# SENSOR_BOARDS.net
KiCad netlist of a schematic drawn in Altium Designer
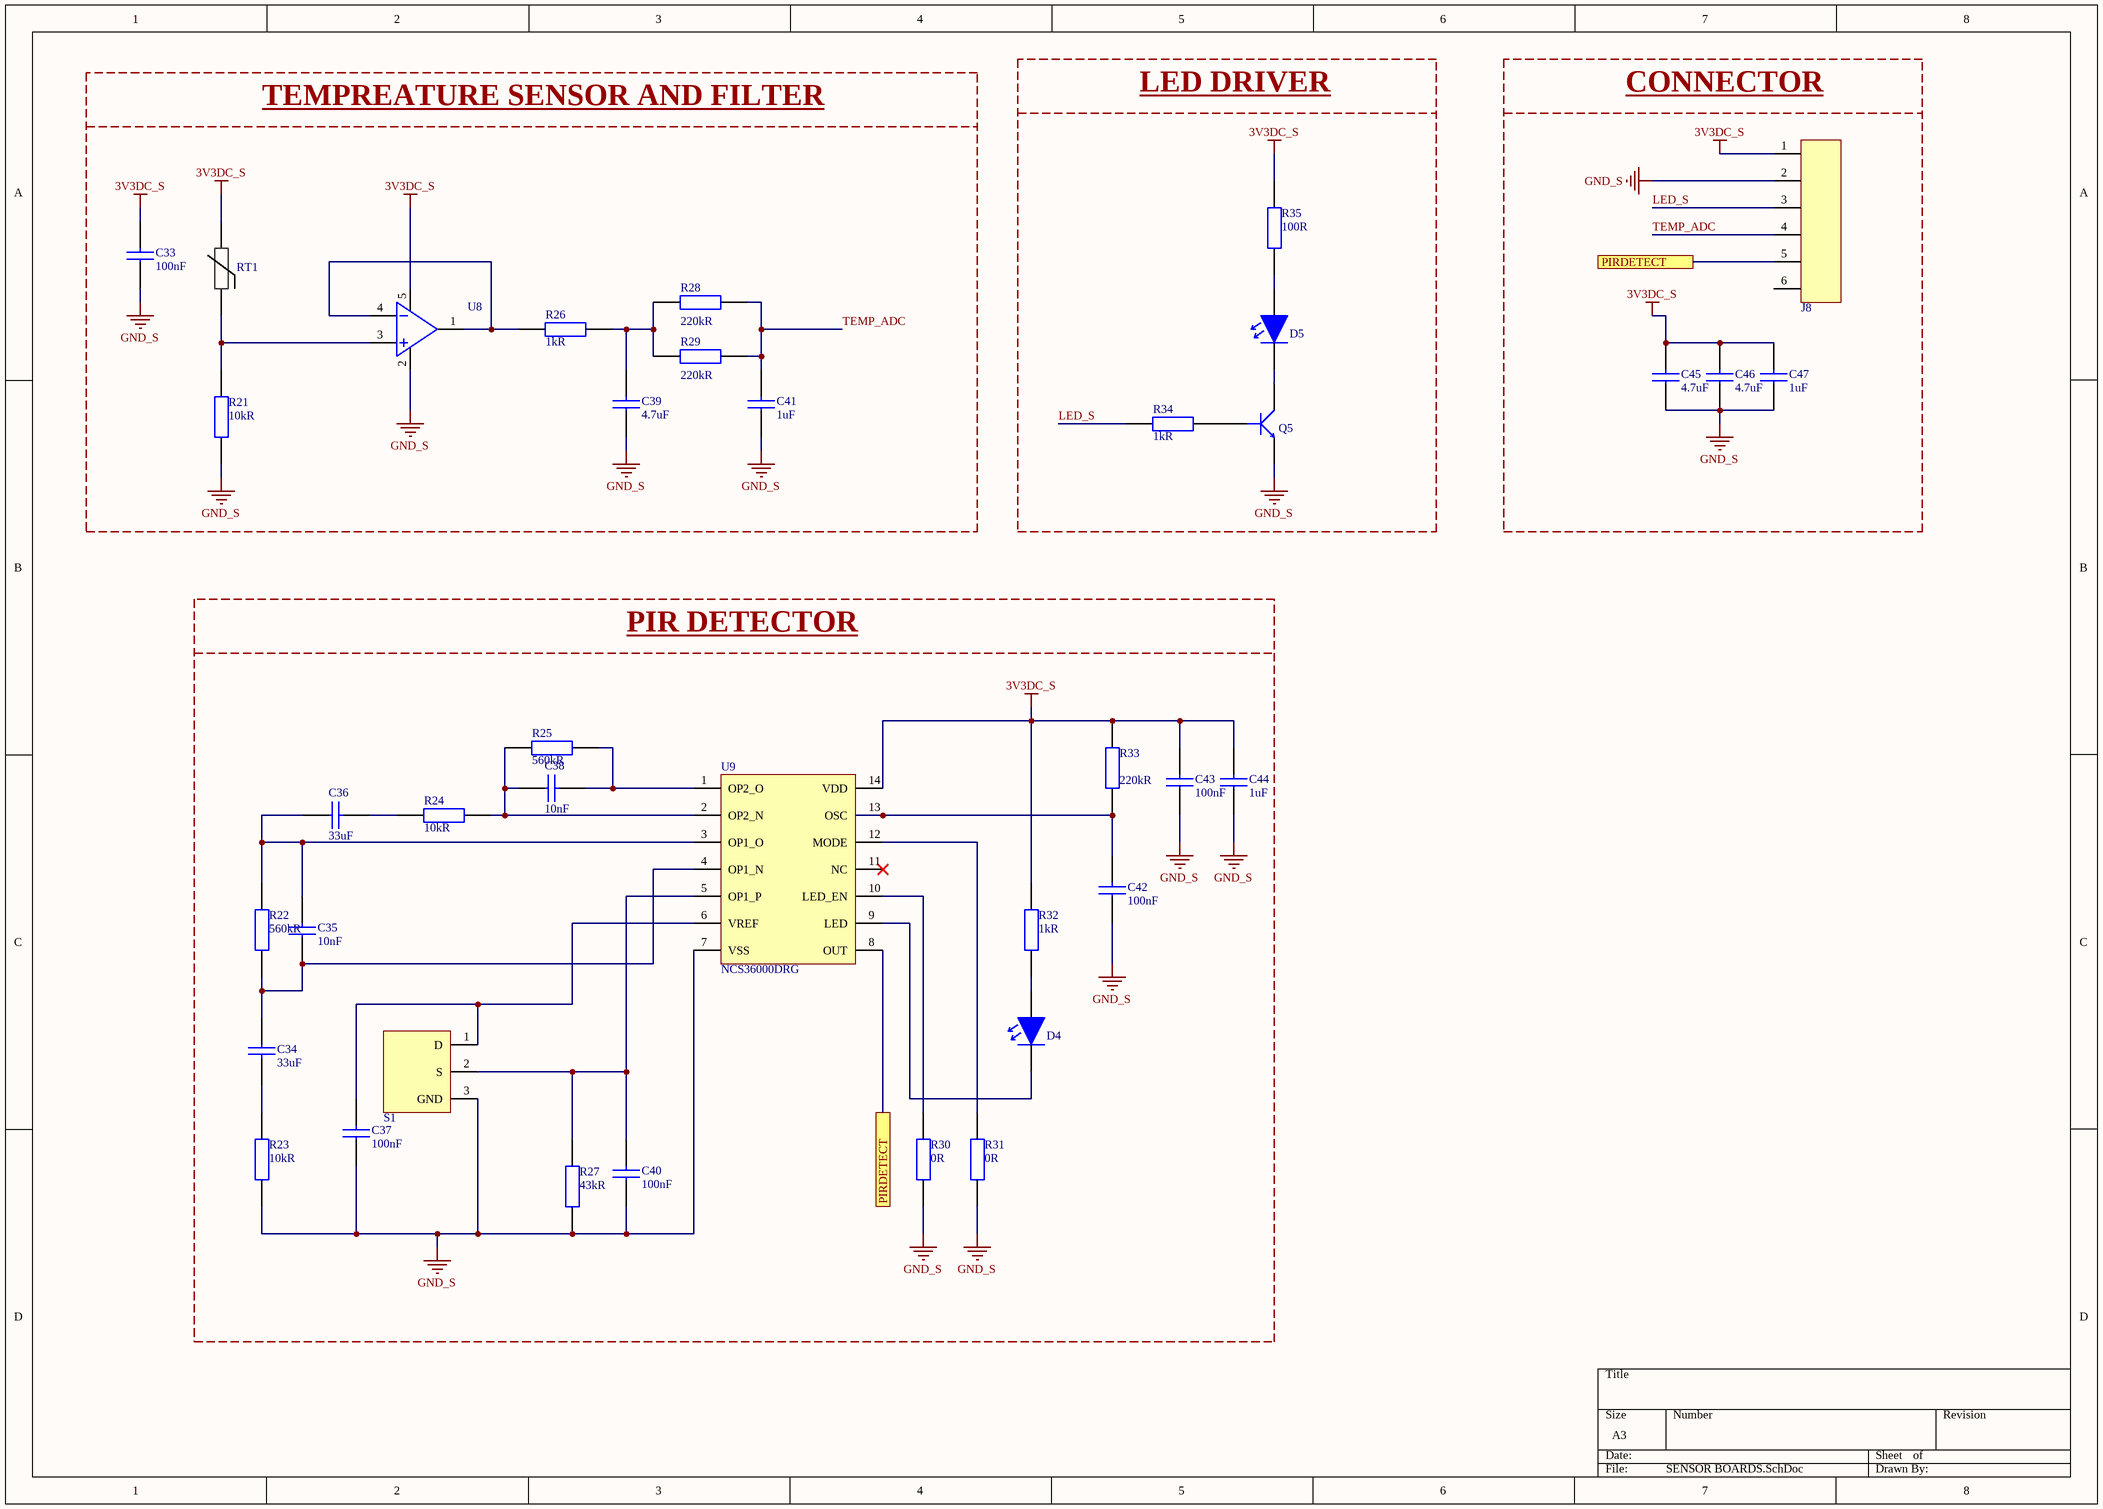
[diagram p0: SENSOR BOARDS.SchDoc]

(export (version "E")
  (design (tool "Eeschema 10.0.6"))
  (components
    (comp (ref "C33")
      (value "C0603C104K5RACTU")
      (footprint "CAP_0603")
      (description "CAP CER 100nF %10 0603 SMD")
      (fields
        (field (name "MANUFACTURER") "KEMET")
        (field (name "TOLERANCE") "10%")
        (field (name "CAPACITANCE") "100nF")
        (field (name "DESIGNED BY") "BERK")
      )
      (libsource (lib "UDEMY_Library") (part "CAP CER 100nF 0603"))
    )
    (comp (ref "C34")
      (value "C3216X5R1E336M160AC")
      (footprint "CAP_1206")
      (description "CAP CER 33uF %20 1206 SMD")
      (fields
        (field (name "MANUFACTURER") "TDK")
        (field (name "TOLERANCE") "20%")
        (field (name "CAPACITANCE") "33uF")
        (field (name "DESIGNED BY") "BERK")
      )
      (libsource (lib "UDEMY_Library") (part "CAP CER 33uF 1206"))
    )
    (comp (ref "C35")
      (value "0603B103K160CT")
      (footprint "CAP_0603")
      (description "CAP CER 10nF %10 0603")
      (fields
        (field (name "MANUFACTURER") "Walsin Technologies")
        (field (name "TOLERANCE") "10%")
        (field (name "CAPACITANCE") "10nF")
        (field (name "DESIGNED BY") "BERK")
      )
      (libsource (lib "UDEMY_Library") (part "CAP CER 10nF 0603"))
    )
    (comp (ref "C36")
      (value "C3216X5R1E336M160AC")
      (footprint "CAP_1206")
      (description "CAP CER 33uF %20 1206 SMD")
      (fields
        (field (name "MANUFACTURER") "TDK")
        (field (name "TOLERANCE") "20%")
        (field (name "CAPACITANCE") "33uF")
        (field (name "DESIGNED BY") "BERK")
      )
      (libsource (lib "UDEMY_Library") (part "CAP CER 33uF 1206"))
    )
    (comp (ref "C37")
      (value "C0603C104K5RACTU")
      (footprint "CAP_0603")
      (description "CAP CER 100nF %10 0603 SMD")
      (fields
        (field (name "MANUFACTURER") "KEMET")
        (field (name "TOLERANCE") "10%")
        (field (name "CAPACITANCE") "100nF")
        (field (name "DESIGNED BY") "BERK")
      )
      (libsource (lib "UDEMY_Library") (part "CAP CER 100nF 0603"))
    )
    (comp (ref "C38")
      (value "0603B103K160CT")
      (footprint "CAP_0603")
      (description "CAP CER 10nF %10 0603")
      (fields
        (field (name "MANUFACTURER") "Walsin Technologies")
        (field (name "TOLERANCE") "10%")
        (field (name "CAPACITANCE") "10nF")
        (field (name "DESIGNED BY") "BERK")
      )
      (libsource (lib "UDEMY_Library") (part "CAP CER 10nF 0603"))
    )
    (comp (ref "C39")
      (value "CL21A475KAQNNNE")
      (footprint "CAP_0805")
      (description "CAP CER 4.7uF %10 0805")
      (fields
        (field (name "MANUFACTURER") "Samsung")
        (field (name "TOLERANCE") "10%")
        (field (name "CAPACITANCE") "4.7uF")
        (field (name "DESIGNED BY") "BERK")
      )
      (libsource (lib "UDEMY_Library") (part "CAP CER 4.7uF 0805"))
    )
    (comp (ref "C40")
      (value "C0603C104K5RACTU")
      (footprint "CAP_0603")
      (description "CAP CER 100nF %10 0603 SMD")
      (fields
        (field (name "MANUFACTURER") "KEMET")
        (field (name "TOLERANCE") "10%")
        (field (name "CAPACITANCE") "100nF")
        (field (name "DESIGNED BY") "BERK")
      )
      (libsource (lib "UDEMY_Library") (part "CAP CER 100nF 0603"))
    )
    (comp (ref "C41")
      (value "CL21B105KBFNNNE")
      (footprint "CAP_0805")
      (description "CAP CER 1uF %10 0805")
      (fields
        (field (name "MANUFACTURER") "Samsung")
        (field (name "TOLERANCE") "10%")
        (field (name "CAPACITANCE") "1uF")
        (field (name "DESIGNED BY") "BERK")
      )
      (libsource (lib "UDEMY_Library") (part "CAP CER 1uF 0805"))
    )
    (comp (ref "C42")
      (value "C0603C104K5RACTU")
      (footprint "CAP_0603")
      (description "CAP CER 100nF %10 0603 SMD")
      (fields
        (field (name "MANUFACTURER") "KEMET")
        (field (name "TOLERANCE") "10%")
        (field (name "CAPACITANCE") "100nF")
        (field (name "DESIGNED BY") "BERK")
      )
      (libsource (lib "UDEMY_Library") (part "CAP CER 100nF 0603"))
    )
    (comp (ref "C43")
      (value "C0603C104K5RACTU")
      (footprint "CAP_0603")
      (description "CAP CER 100nF %10 0603 SMD")
      (fields
        (field (name "MANUFACTURER") "KEMET")
        (field (name "TOLERANCE") "10%")
        (field (name "CAPACITANCE") "100nF")
        (field (name "DESIGNED BY") "BERK")
      )
      (libsource (lib "UDEMY_Library") (part "CAP CER 100nF 0603"))
    )
    (comp (ref "C44")
      (value "CL21B105KBFNNNE")
      (footprint "CAP_0805")
      (description "CAP CER 1uF %10 0805")
      (fields
        (field (name "MANUFACTURER") "Samsung")
        (field (name "TOLERANCE") "10%")
        (field (name "CAPACITANCE") "1uF")
        (field (name "DESIGNED BY") "BERK")
      )
      (libsource (lib "UDEMY_Library") (part "CAP CER 1uF 0805"))
    )
    (comp (ref "C45")
      (value "CL21A475KAQNNNE")
      (footprint "CAP_0805")
      (description "CAP CER 4.7uF %10 0805")
      (fields
        (field (name "MANUFACTURER") "Samsung")
        (field (name "TOLERANCE") "10%")
        (field (name "CAPACITANCE") "4.7uF")
        (field (name "DESIGNED BY") "BERK")
      )
      (libsource (lib "UDEMY_Library") (part "CAP CER 4.7uF 0805"))
    )
    (comp (ref "C46")
      (value "CL21A475KAQNNNE")
      (footprint "CAP_0805")
      (description "CAP CER 4.7uF %10 0805")
      (fields
        (field (name "MANUFACTURER") "Samsung")
        (field (name "TOLERANCE") "10%")
        (field (name "CAPACITANCE") "4.7uF")
        (field (name "DESIGNED BY") "BERK")
      )
      (libsource (lib "UDEMY_Library") (part "CAP CER 4.7uF 0805"))
    )
    (comp (ref "C47")
      (value "CL21B105KBFNNNE")
      (footprint "CAP_0805")
      (description "CAP CER 1uF %10 0805")
      (fields
        (field (name "MANUFACTURER") "Samsung")
        (field (name "TOLERANCE") "10%")
        (field (name "CAPACITANCE") "1uF")
        (field (name "DESIGNED BY") "BERK")
      )
      (libsource (lib "UDEMY_Library") (part "CAP CER 1uF 0805"))
    )
    (comp (ref "D4")
      (value "LTST-C171GKT")
      (footprint "LED_GREEN_0805")
      (description "Green 0805 130 º Min 5 mcd Typical 12 mcd Water Clear Lens SMT LED")
      (fields (field (name "MANUFACTURER") "Vishay Lite-On") (field (name "DESIGNED BY") "BERK"))
      (libsource (lib "UDEMY_Library") (part "LED GREEN 0805"))
    )
    (comp (ref "D5")
      (value "LH R974-LP-1")
      (footprint "LED_RED_0805")
      (description "LED Uni-Color Hyper Red 660nm 2-Pin Chip 0805(2012Metric) T/R")
      (fields (field (name "MANUFACTURER") "Osram Opto") (field (name "DESIGNED BY") "BERK"))
      (libsource (lib "UDEMY_Library") (part "LED RED 0805"))
    )
    (comp (ref "J8")
      (value "64800611622")
      (footprint "64800611622")
      (description "1.50mm 6PIN Connector")
      (fields (field (name "MANUFACTURER") "Wurth Electronics"))
      (libsource (lib "UDEMY_Library") (part "64800611622_conn_6pin"))
    )
    (comp (ref "Q5")
      (value "MMBT3904-7-F")
      (footprint "SOT-23F")
      (description "Transistor General Purpose BJT NPN 40 Volt 0.2A Automotive 3-Pin SOT-23")
      (fields (field (name "MANUFACTURER") "Diodes Zetex") (field (name "DESIGNED BY") "BERK"))
      (libsource (lib "UDEMY_Library") (part "MMBT3904-7-F"))
    )
    (comp (ref "R21")
      (value "RC0603FR-0710KL")
      (footprint "RES_0603")
      (description "RES 10K %1 OHM 0603 SMD")
      (fields
        (field (name "MANUFACTURER") "Yageo")
        (field (name "TOLERANCE") "1%")
        (field (name "RESISTANCE") "10kR")
        (field (name "DESIGNED BY") "BERK")
      )
      (libsource (lib "") (part "RES 10K OHM 0603_1"))
    )
    (comp (ref "R22")
      (value "RC0603JR-07560KL")
      (footprint "RES_0603")
      (description "RES SMD 560K OHM 5% 1/10W 0603")
      (fields
        (field (name "MANUFACTURER") "Yageo")
        (field (name "TOLERANCE") "5%")
        (field (name "RESISTANCE") "560kR")
        (field (name "DESIGNED BY") "BERK")
      )
      (libsource (lib "") (part "RES 560K OHM 0603_1"))
    )
    (comp (ref "R23")
      (value "RC0603FR-0710KL")
      (footprint "RES_0603")
      (description "RES 10K %1 OHM 0603 SMD")
      (fields
        (field (name "MANUFACTURER") "Yageo")
        (field (name "TOLERANCE") "1%")
        (field (name "RESISTANCE") "10kR")
        (field (name "DESIGNED BY") "BERK")
      )
      (libsource (lib "UDEMY_Library") (part "RES 10K OHM 0603"))
    )
    (comp (ref "R24")
      (value "RC0603FR-0710KL")
      (footprint "RES_0603")
      (description "RES 10K %1 OHM 0603 SMD")
      (fields
        (field (name "MANUFACTURER") "Yageo")
        (field (name "TOLERANCE") "1%")
        (field (name "RESISTANCE") "10kR")
        (field (name "DESIGNED BY") "BERK")
      )
      (libsource (lib "") (part "RES 10K OHM 0603_2"))
    )
    (comp (ref "R25")
      (value "RC0603JR-07560KL")
      (footprint "RES_0603")
      (description "RES SMD 560K OHM 5% 1/10W 0603")
      (fields
        (field (name "MANUFACTURER") "Yageo")
        (field (name "TOLERANCE") "5%")
        (field (name "RESISTANCE") "560kR")
        (field (name "DESIGNED BY") "BERK")
      )
      (libsource (lib "UDEMY_Library") (part "RES 560K OHM 0603"))
    )
    (comp (ref "R26")
      (value "RC0603FR-0710KL")
      (footprint "RES_0603")
      (description "RES 1K %1 OHM 0603 SMD")
      (fields
        (field (name "MANUFACTURER") "Yageo")
        (field (name "MANUFACTURER PART NUMBER") "RC0603JR-071KL")
        (field (name "RESISTANCE") "1kR")
        (field (name "DESIGNED BY") "BERK")
      )
      (libsource (lib "") (part "RES 1K OHM 0603_2"))
    )
    (comp (ref "R27")
      (value "RC0603JR-0743KL")
      (footprint "RES_0603")
      (description "RES 43K %5 OHM 0603 SMD")
      (fields
        (field (name "MANUFACTURER") "Yageo")
        (field (name "TOLERANCE") "5%")
        (field (name "RESISTANCE") "43kR")
        (field (name "DESIGNED BY") "BERK")
      )
      (libsource (lib "UDEMY_Library") (part "RES 43K OHM 0603"))
    )
    (comp (ref "R28")
      (value "RC0603JR-07220KL")
      (footprint "RES_0603")
      (description "RES 220K %5 OHM 0603 SMD")
      (fields
        (field (name "MANUFACTURER") "Yageo")
        (field (name "TOLERANCE") "5%")
        (field (name "RESISTANCE") "220kR")
      )
      (libsource (lib "UDEMY_Library") (part "RES 220K OHM 0603"))
    )
    (comp (ref "R29")
      (value "RC0603JR-07220KL")
      (footprint "RES_0603")
      (description "RES 220K %5 OHM 0603 SMD")
      (fields
        (field (name "MANUFACTURER") "Yageo")
        (field (name "TOLERANCE") "5%")
        (field (name "RESISTANCE") "220kR")
      )
      (libsource (lib "UDEMY_Library") (part "RES 220K OHM 0603"))
    )
    (comp (ref "R30")
      (value "RC0603JR-070RL")
      (footprint "RES_0603")
      (description "RES 0 %1 OHM 0603 SMD")
      (fields
        (field (name "MANUFACTURER") "Yageo")
        (field (name "TOLERANCE") "1%")
        (field (name "RESISTANCE") "0R")
        (field (name "DESIGNED BY") "BERK")
      )
      (libsource (lib "UDEMY_Library") (part "RES 0 OHM 0603"))
    )
    (comp (ref "R31")
      (value "RC0603JR-070RL")
      (footprint "RES_0603")
      (description "RES 0 %1 OHM 0603 SMD")
      (fields
        (field (name "MANUFACTURER") "Yageo")
        (field (name "TOLERANCE") "1%")
        (field (name "RESISTANCE") "0R")
        (field (name "DESIGNED BY") "BERK")
      )
      (libsource (lib "UDEMY_Library") (part "RES 0 OHM 0603"))
    )
    (comp (ref "R32")
      (value "RC0603FR-0710KL")
      (footprint "RES_0603")
      (description "RES 1K %1 OHM 0603 SMD")
      (fields
        (field (name "MANUFACTURER") "Yageo")
        (field (name "MANUFACTURER PART NUMBER") "RC0603JR-071KL")
        (field (name "RESISTANCE") "1kR")
        (field (name "DESIGNED BY") "BERK")
      )
      (libsource (lib "") (part "RES 1K OHM 0603_1"))
    )
    (comp (ref "R33")
      (value "RC0603JR-07220KL")
      (footprint "RES_0603")
      (description "RES 220K %5 OHM 0603 SMD")
      (fields
        (field (name "MANUFACTURER") "Yageo")
        (field (name "TOLERANCE") "5%")
        (field (name "RESISTANCE") "220kR")
      )
      (libsource (lib "") (part "RES 220K OHM 0603_1"))
    )
    (comp (ref "R34")
      (value "RC0603FR-0710KL")
      (footprint "RES_0603")
      (description "RES 1K %1 OHM 0603 SMD")
      (fields
        (field (name "MANUFACTURER") "Yageo")
        (field (name "MANUFACTURER PART NUMBER") "RC0603JR-071KL")
        (field (name "RESISTANCE") "1kR")
        (field (name "DESIGNED BY") "BERK")
      )
      (libsource (lib "UDEMY_Library") (part "RES 1K OHM 0603"))
    )
    (comp (ref "R35")
      (value "RC0603JR-07100RL")
      (footprint "RES_0603")
      (description "RES 100 %5 OHM 0603 SMD")
      (fields
        (field (name "MANUFACTURER") "Yageo")
        (field (name "TOLERANCE") "5%")
        (field (name "RESISTANCE") "100R")
        (field (name "DESIGNED BY") "BERK")
      )
      (libsource (lib "UDEMY_Library") (part "RES 100 OHM 0603"))
    )
    (comp (ref "RT1")
      (value "TFPT1206L1002FM")
      (footprint "RES_1206")
      (description "Thermistor PTC 10K Ohm 1% 1206")
      (fields
        (field (name "MANUFACTURER") "Vishay Dale")
        (field (name "TOLERANCE") "1%")
        (field (name "DESIGNED BY") "BERK")
      )
      (libsource (lib "UDEMY_Library") (part "TFPT1206L1002FM"))
    )
    (comp (ref "S1")
      (value "LHI 878/3902")
      (footprint "LHI 878")
      (description "SENSOR PYRO DETECTOR DUAL MOTION")
      (fields (field (name "DESIGNED BY") "BERK"))
      (libsource (lib "UDEMY_Library") (part "LHI 878/3902"))
    )
    (comp (ref "U8")
      (value "OPA314AIDBVR")
      (footprint "SOT23-5")
      (description "Op Amp OPA314")
      (fields (field (name "MANUFACTURER") "Texas Instruments") (field (name "DESIGNED BY") "BERK"))
      (libsource (lib "UDEMY_Library") (part "OPA314"))
    )
    (comp (ref "U9")
      (value "NCS36000DRG")
      (footprint "SOIC14")
      (description "PIR Controller Low Noise Amplifiers and LDO Regulator 14-Pin SOIC N T/R")
      (fields (field (name "MANUFACTURER") "ON Semiconductor") (field (name "DESIGNED BY") "BERK"))
      (libsource (lib "UDEMY_Library") (part "NCS36000"))
    )
  )
  (nets
    (net (code "1") (name "/LED_S") (class "Default")
      (node (ref "J8") (pin "3") (pintype "power_in"))
      (node (ref "R34") (pin "1") (pinfunction "1_1") (pintype "passive"))
    )
    (net (code "2") (name "/PIRDETECT") (class "Default")
      (node (ref "J8") (pin "5") (pintype "power_in"))
      (node (ref "U9") (pin "8") (pinfunction "OUT_8") (pintype "passive"))
    )
    (net (code "3") (name "/TEMP_ADC") (class "Default")
      (node (ref "C41") (pin "2") (pinfunction "2_2") (pintype "passive"))
      (node (ref "J8") (pin "4") (pintype "power_in"))
      (node (ref "R28") (pin "2") (pinfunction "2_2") (pintype "passive"))
      (node (ref "R29") (pin "2") (pinfunction "2_2") (pintype "passive"))
    )
    (net (code "4") (name "3V3DC_S") (class "Default")
      (node (ref "C33") (pin "2") (pinfunction "2_2") (pintype "passive"))
      (node (ref "C43") (pin "2") (pinfunction "2_2") (pintype "passive"))
      (node (ref "C44") (pin "2") (pinfunction "2_2") (pintype "passive"))
      (node (ref "C45") (pin "2") (pinfunction "2_2") (pintype "passive"))
      (node (ref "C46") (pin "2") (pinfunction "2_2") (pintype "passive"))
      (node (ref "C47") (pin "2") (pinfunction "2_2") (pintype "passive"))
      (node (ref "J8") (pin "1") (pintype "power_in"))
      (node (ref "R32") (pin "2") (pinfunction "2_2") (pintype "passive"))
      (node (ref "R33") (pin "1") (pinfunction "1_1") (pintype "passive"))
      (node (ref "R35") (pin "2") (pinfunction "2_2") (pintype "passive"))
      (node (ref "RT1") (pin "2") (pinfunction "2_2") (pintype "passive"))
      (node (ref "U8") (pin "5") (pinfunction "5_5") (pintype "passive"))
      (node (ref "U9") (pin "14") (pinfunction "VDD_14") (pintype "passive"))
    )
    (net (code "5") (name "GND_S") (class "Default")
      (node (ref "C33") (pin "1") (pinfunction "1_1") (pintype "passive"))
      (node (ref "C37") (pin "1") (pinfunction "1_1") (pintype "passive"))
      (node (ref "C39") (pin "1") (pinfunction "1_1") (pintype "passive"))
      (node (ref "C40") (pin "1") (pinfunction "1_1") (pintype "passive"))
      (node (ref "C41") (pin "1") (pinfunction "1_1") (pintype "passive"))
      (node (ref "C42") (pin "1") (pinfunction "1_1") (pintype "passive"))
      (node (ref "C43") (pin "1") (pinfunction "1_1") (pintype "passive"))
      (node (ref "C44") (pin "1") (pinfunction "1_1") (pintype "passive"))
      (node (ref "C45") (pin "1") (pinfunction "1_1") (pintype "passive"))
      (node (ref "C46") (pin "1") (pinfunction "1_1") (pintype "passive"))
      (node (ref "C47") (pin "1") (pinfunction "1_1") (pintype "passive"))
      (node (ref "J8") (pin "2") (pintype "power_in"))
      (node (ref "Q5") (pin "2") (pinfunction "E_2") (pintype "power_in"))
      (node (ref "R21") (pin "1") (pinfunction "1_1") (pintype "passive"))
      (node (ref "R23") (pin "2") (pinfunction "2_2") (pintype "passive"))
      (node (ref "R27") (pin "1") (pinfunction "1_1") (pintype "passive"))
      (node (ref "R30") (pin "1") (pinfunction "1_1") (pintype "passive"))
      (node (ref "R31") (pin "1") (pinfunction "1_1") (pintype "passive"))
      (node (ref "S1") (pin "3") (pinfunction "GND_3") (pintype "passive"))
      (node (ref "U8") (pin "2") (pinfunction "2_2") (pintype "passive"))
      (node (ref "U9") (pin "7") (pinfunction "VSS_7") (pintype "passive"))
    )
    (net (code "6") (name "Net-(C34-Pad2)") (class "Default")
      (node (ref "C34") (pin "2") (pinfunction "2_2") (pintype "passive"))
      (node (ref "R23") (pin "1") (pinfunction "1_1") (pintype "passive"))
    )
    (net (code "7") (name "Net-(C36-Pad2)") (class "Default")
      (node (ref "C36") (pin "2") (pinfunction "2_2") (pintype "passive"))
      (node (ref "R24") (pin "1") (pinfunction "1_1") (pintype "passive"))
    )
    (net (code "8") (name "Net-(C39-Pad2)") (class "Default")
      (node (ref "C39") (pin "2") (pinfunction "2_2") (pintype "passive"))
      (node (ref "R26") (pin "1") (pinfunction "1_1") (pintype "passive"))
      (node (ref "R28") (pin "1") (pinfunction "1_1") (pintype "passive"))
      (node (ref "R29") (pin "1") (pinfunction "1_1") (pintype "passive"))
    )
    (net (code "9") (name "Net-(D4-Pad2)") (class "Default")
      (node (ref "D4") (pin "2") (pinfunction "2_2") (pintype "power_in"))
      (node (ref "R32") (pin "1") (pinfunction "1_1") (pintype "passive"))
    )
    (net (code "10") (name "Net-(D5-Pad2)") (class "Default")
      (node (ref "D5") (pin "2") (pinfunction "2_2") (pintype "power_in"))
      (node (ref "R35") (pin "1") (pinfunction "1_1") (pintype "passive"))
    )
    (net (code "11") (name "Net-(Q5-B)") (class "Default")
      (node (ref "Q5") (pin "1") (pinfunction "B_1") (pintype "power_in"))
      (node (ref "R34") (pin "2") (pinfunction "2_2") (pintype "passive"))
    )
    (net (code "12") (name "Net-(Q5-C)") (class "Default")
      (node (ref "D5") (pin "1") (pinfunction "1_1") (pintype "power_in"))
      (node (ref "Q5") (pin "3") (pinfunction "C_3") (pintype "power_in"))
    )
    (net (code "13") (name "Net-(R21-Pad2)") (class "Default")
      (node (ref "R21") (pin "2") (pinfunction "2_2") (pintype "passive"))
      (node (ref "RT1") (pin "1") (pinfunction "1_1") (pintype "passive"))
      (node (ref "U8") (pin "3") (pinfunction "3_3") (pintype "passive"))
    )
    (net (code "14") (name "Net-(R26-Pad2)") (class "Default")
      (node (ref "R26") (pin "2") (pinfunction "2_2") (pintype "passive"))
      (node (ref "U8") (pin "1") (pinfunction "1_1") (pintype "passive"))
      (node (ref "U8") (pin "4") (pinfunction "4_4") (pintype "passive"))
    )
    (net (code "15") (name "Net-(S1-D)") (class "Default")
      (node (ref "C37") (pin "2") (pinfunction "2_2") (pintype "passive"))
      (node (ref "S1") (pin "1") (pinfunction "D_1") (pintype "passive"))
      (node (ref "U9") (pin "6") (pinfunction "VREF_6") (pintype "passive"))
    )
    (net (code "16") (name "Net-(S1-S)") (class "Default")
      (node (ref "C40") (pin "2") (pinfunction "2_2") (pintype "passive"))
      (node (ref "R27") (pin "2") (pinfunction "2_2") (pintype "passive"))
      (node (ref "S1") (pin "2") (pinfunction "S_2") (pintype "passive"))
      (node (ref "U9") (pin "5") (pinfunction "OP1_P_5") (pintype "passive"))
    )
    (net (code "17") (name "Net-(U9-LED)") (class "Default")
      (node (ref "D4") (pin "1") (pinfunction "1_1") (pintype "power_in"))
      (node (ref "U9") (pin "9") (pinfunction "LED_9") (pintype "passive"))
    )
    (net (code "18") (name "Net-(U9-LED_EN)") (class "Default")
      (node (ref "R30") (pin "2") (pinfunction "2_2") (pintype "passive"))
      (node (ref "U9") (pin "10") (pinfunction "LED_EN_10") (pintype "passive"))
    )
    (net (code "19") (name "Net-(U9-MODE)") (class "Default")
      (node (ref "R31") (pin "2") (pinfunction "2_2") (pintype "passive"))
      (node (ref "U9") (pin "12") (pinfunction "MODE_12") (pintype "passive"))
    )
    (net (code "20") (name "Net-(U9-OP1_N)") (class "Default")
      (node (ref "C34") (pin "1") (pinfunction "1_1") (pintype "passive"))
      (node (ref "C35") (pin "1") (pinfunction "1_1") (pintype "passive"))
      (node (ref "R22") (pin "1") (pinfunction "1_1") (pintype "passive"))
      (node (ref "U9") (pin "4") (pinfunction "OP1_N_4") (pintype "passive"))
    )
    (net (code "21") (name "Net-(U9-OP1_O)") (class "Default")
      (node (ref "C35") (pin "2") (pinfunction "2_2") (pintype "passive"))
      (node (ref "C36") (pin "1") (pinfunction "1_1") (pintype "passive"))
      (node (ref "R22") (pin "2") (pinfunction "2_2") (pintype "passive"))
      (node (ref "U9") (pin "3") (pinfunction "OP1_O_3") (pintype "passive"))
    )
    (net (code "22") (name "Net-(U9-OP2_N)") (class "Default")
      (node (ref "C38") (pin "1") (pinfunction "1_1") (pintype "passive"))
      (node (ref "R24") (pin "2") (pinfunction "2_2") (pintype "passive"))
      (node (ref "R25") (pin "1") (pinfunction "1_1") (pintype "passive"))
      (node (ref "U9") (pin "2") (pinfunction "OP2_N_2") (pintype "passive"))
    )
    (net (code "23") (name "Net-(U9-OP2_O)") (class "Default")
      (node (ref "C38") (pin "2") (pinfunction "2_2") (pintype "passive"))
      (node (ref "R25") (pin "2") (pinfunction "2_2") (pintype "passive"))
      (node (ref "U9") (pin "1") (pinfunction "OP2_O_1") (pintype "passive"))
    )
    (net (code "24") (name "Net-(U9-OSC)") (class "Default")
      (node (ref "C42") (pin "2") (pinfunction "2_2") (pintype "passive"))
      (node (ref "R33") (pin "2") (pinfunction "2_2") (pintype "passive"))
      (node (ref "U9") (pin "13") (pinfunction "OSC_13") (pintype "passive"))
    )
    (net (code "25") (name "unconnected-(J8-Pad6)") (class "Default")
      (node (ref "J8") (pin "6") (pintype "power_in"))
    )
    (net (code "26") (name "unconnected-(U9-NC-Pad11)") (class "Default")
      (node (ref "U9") (pin "11") (pinfunction "NC_11") (pintype "passive+no_connect"))
    )
  )
)
